# tick-pi-mk-1_0.net
KiCad netlist of a schematic drawn in EAGLE
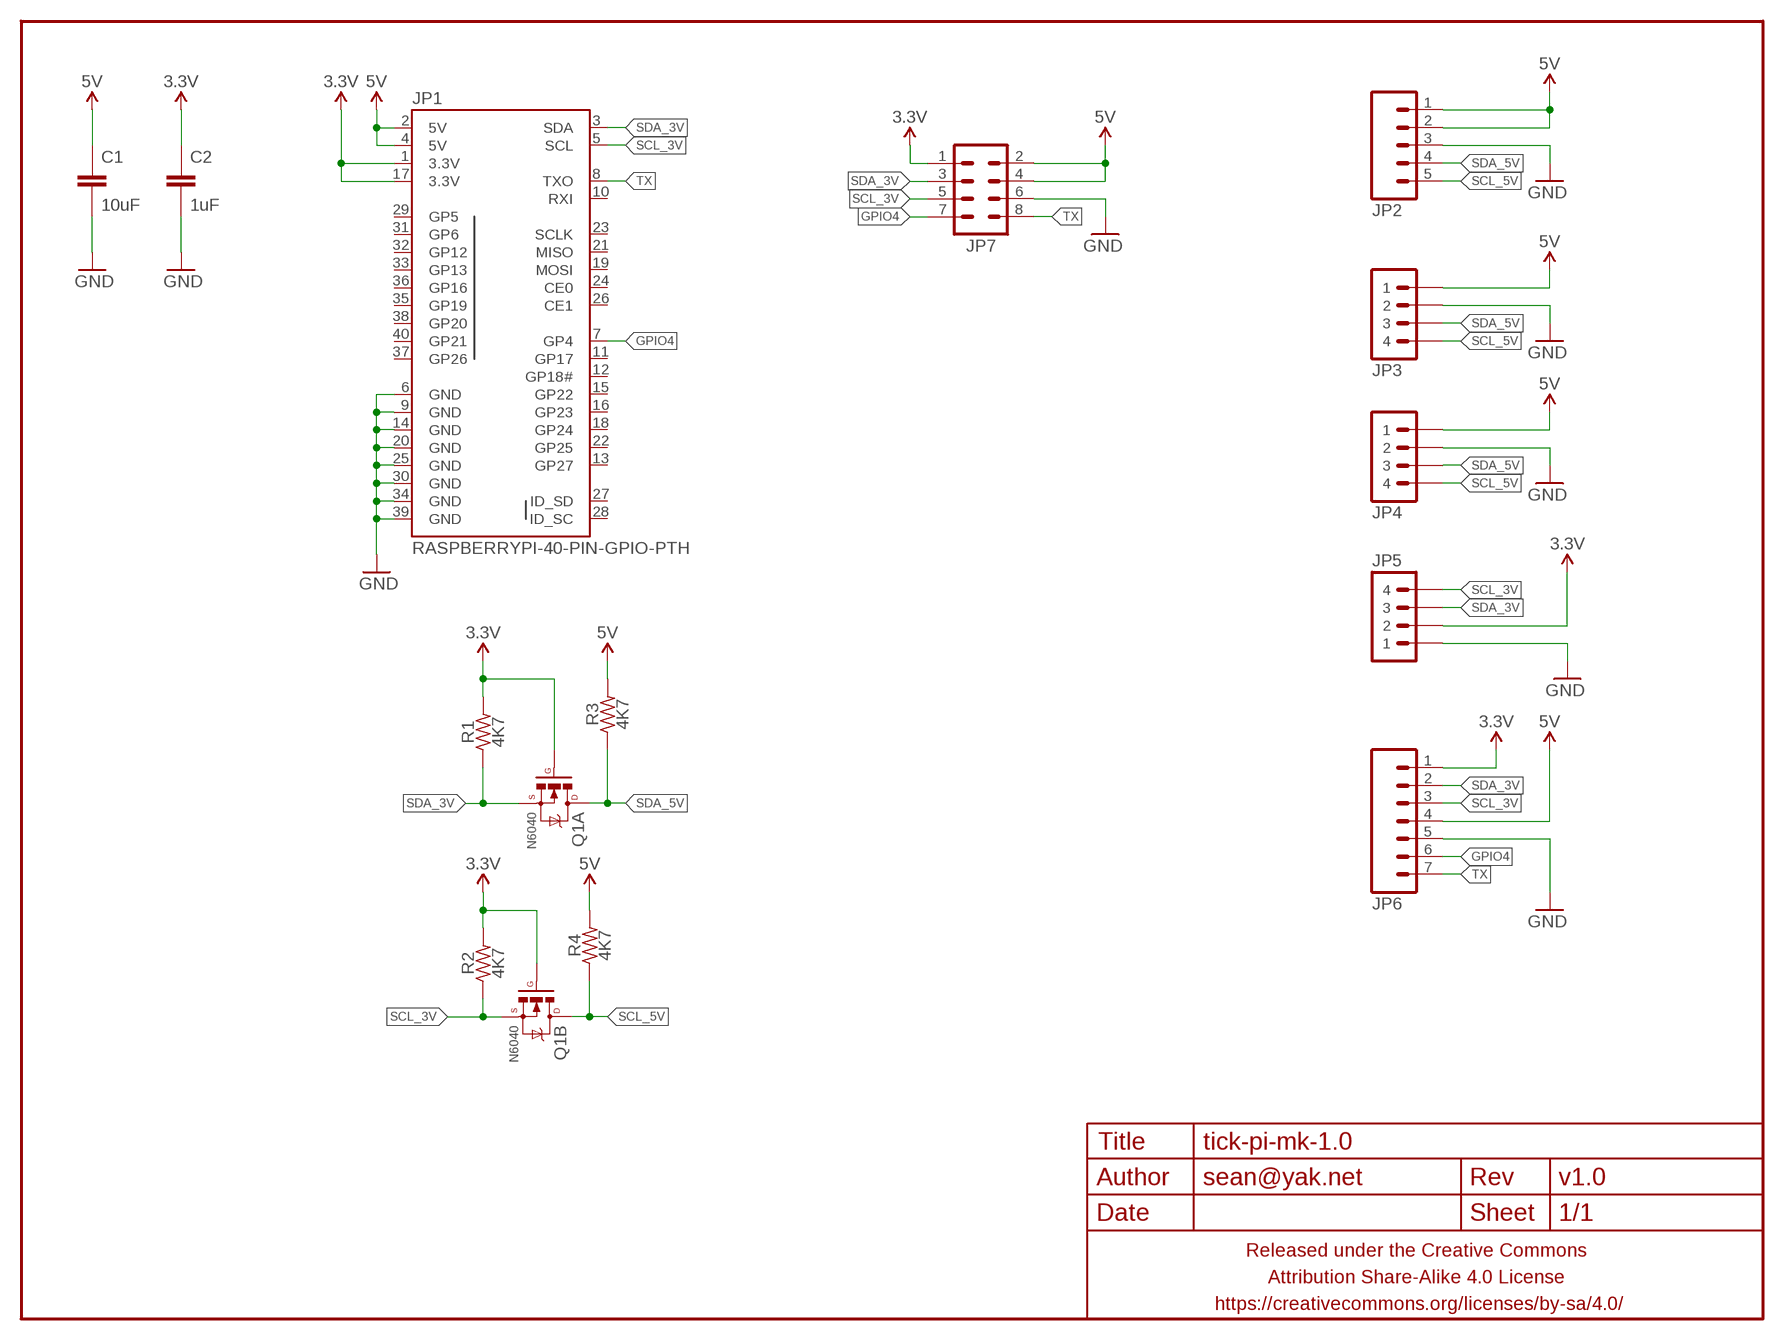
[diagram p0: schematic, sheet 1]

(export (version "E")
  (design (tool "Eeschema 10.0.6"))
  (components
    (comp (ref "C1")
      (value "10uF")
      (footprint "eagle-import:C0805-TIGHTER")
      (libsource (lib "eagle-import") (part "CAPACITOR-CERAMICC0805-TIGHTER"))
    )
    (comp (ref "C2")
      (value "1uF")
      (footprint "eagle-import:C0805-TIGHTER")
      (libsource (lib "eagle-import") (part "CAPACITOR-CERAMICC0805-TIGHTER"))
    )
    (comp (ref "FRAME1")
      (value "FRAME-LETTERNO_PACKAGE")
      (footprint "eagle-import:DUMMY")
      (fields (field (name "DESIGNER") "sean@yak.net") (field (name "VERSION") "v1.0"))
      (libsource (lib "eagle-import") (part "FRAME-LETTERNO_PACKAGE"))
    )
    (comp (ref "JP1")
      (value "RASPBERRYPI-40-PIN-GPIO-PTH")
      (footprint "eagle-import:2X20_PTH")
      (libsource (lib "eagle-import") (part "RASPBERRYPI-40-PIN-GPIO-PTH"))
    )
    (comp (ref "JP2")
      (value "M05PTH-CENTERED-RA-FEMALE")
      (footprint "eagle-import:1X05_PTH_CENTERED_RA_FEMALE")
      (libsource (lib "eagle-import") (part "M05PTH-CENTERED-RA-FEMALE"))
    )
    (comp (ref "JP3")
      (value "M04PTH")
      (footprint "eagle-import:1X04-PTH-VERT")
      (libsource (lib "eagle-import") (part "M04PTH"))
    )
    (comp (ref "JP4")
      (value "M04PTH")
      (footprint "eagle-import:1X04-PTH-VERT")
      (libsource (lib "eagle-import") (part "M04PTH"))
    )
    (comp (ref "JP5")
      (value "M04PTH")
      (footprint "eagle-import:1X04-PTH-VERT")
      (libsource (lib "eagle-import") (part "M04PTH"))
    )
    (comp (ref "JP6")
      (value "M07")
      (footprint "eagle-import:1X07")
      (libsource (lib "eagle-import") (part "M07"))
    )
    (comp (ref "JP7")
      (value "M04X2PTH")
      (footprint "eagle-import:2X4_PTH")
      (libsource (lib "eagle-import") (part "M04X2PTH"))
    )
    (comp (ref "Q1")
      (value "N6040")
      (footprint "eagle-import:SO08")
      (libsource (lib "eagle-import") (part "MOSFET-NCHANNEL-DUALSOIC8"))
    )
    (comp (ref "R1")
      (value "4K7")
      (footprint "eagle-import:R0603")
      (libsource (lib "eagle-import") (part "RESISTORR0603"))
    )
    (comp (ref "R2")
      (value "4K7")
      (footprint "eagle-import:R0603")
      (libsource (lib "eagle-import") (part "RESISTORR0603"))
    )
    (comp (ref "R3")
      (value "4K7")
      (footprint "eagle-import:R0603")
      (libsource (lib "eagle-import") (part "RESISTORR0603"))
    )
    (comp (ref "R4")
      (value "4K7")
      (footprint "eagle-import:R0603")
      (libsource (lib "eagle-import") (part "RESISTORR0603"))
    )
  )
  (nets
    (net (code "1") (name "3.3V") (class "Default")
      (node (ref "C2") (pin "1") (pinfunction "1_1") (pintype "passive"))
      (node (ref "JP1") (pin "1") (pinfunction "3.3V_1") (pintype "power_in"))
      (node (ref "JP1") (pin "17") (pinfunction "3.3V_17") (pintype "power_in"))
      (node (ref "JP5") (pin "2") (pinfunction "2_2") (pintype "passive"))
      (node (ref "JP6") (pin "1") (pinfunction "1_1") (pintype "passive"))
      (node (ref "JP7") (pin "1") (pinfunction "1_1") (pintype "passive"))
      (node (ref "Q1") (pin "2") (pinfunction "G_2") (pintype "passive"))
      (node (ref "Q1") (pin "4") (pinfunction "G_4") (pintype "passive"))
      (node (ref "R1") (pin "2") (pinfunction "2_2") (pintype "passive"))
      (node (ref "R2") (pin "2") (pinfunction "2_2") (pintype "passive"))
    )
    (net (code "2") (name "5V") (class "Default")
      (node (ref "C1") (pin "1") (pinfunction "1_1") (pintype "passive"))
      (node (ref "JP1") (pin "2") (pinfunction "5V_2") (pintype "power_in"))
      (node (ref "JP1") (pin "4") (pinfunction "5V_4") (pintype "power_in"))
      (node (ref "JP2") (pin "1") (pinfunction "1_1") (pintype "passive"))
      (node (ref "JP2") (pin "2") (pinfunction "2_2") (pintype "passive"))
      (node (ref "JP3") (pin "1") (pinfunction "1_1") (pintype "passive"))
      (node (ref "JP4") (pin "1") (pinfunction "1_1") (pintype "passive"))
      (node (ref "JP6") (pin "4") (pinfunction "4_4") (pintype "passive"))
      (node (ref "JP7") (pin "2") (pinfunction "2_2") (pintype "passive"))
      (node (ref "JP7") (pin "4") (pinfunction "4_4") (pintype "passive"))
      (node (ref "R3") (pin "2") (pinfunction "2_2") (pintype "passive"))
      (node (ref "R4") (pin "2") (pinfunction "2_2") (pintype "passive"))
    )
    (net (code "3") (name "GND") (class "Default")
      (node (ref "C1") (pin "2") (pinfunction "2_2") (pintype "passive"))
      (node (ref "C2") (pin "2") (pinfunction "2_2") (pintype "passive"))
      (node (ref "JP1") (pin "14") (pinfunction "GND_14") (pintype "power_in"))
      (node (ref "JP1") (pin "20") (pinfunction "GND_20") (pintype "power_in"))
      (node (ref "JP1") (pin "25") (pinfunction "GND_25") (pintype "power_in"))
      (node (ref "JP1") (pin "30") (pinfunction "GND_30") (pintype "power_in"))
      (node (ref "JP1") (pin "34") (pinfunction "GND_34") (pintype "power_in"))
      (node (ref "JP1") (pin "39") (pinfunction "GND_39") (pintype "power_in"))
      (node (ref "JP1") (pin "6") (pinfunction "GND_6") (pintype "power_in"))
      (node (ref "JP1") (pin "9") (pinfunction "GND_9") (pintype "power_in"))
      (node (ref "JP2") (pin "3") (pinfunction "3_3") (pintype "passive"))
      (node (ref "JP3") (pin "2") (pinfunction "2_2") (pintype "passive"))
      (node (ref "JP4") (pin "2") (pinfunction "2_2") (pintype "passive"))
      (node (ref "JP5") (pin "1") (pinfunction "1_1") (pintype "passive"))
      (node (ref "JP6") (pin "5") (pinfunction "5_5") (pintype "passive"))
      (node (ref "JP7") (pin "6") (pinfunction "6_6") (pintype "passive"))
    )
    (net (code "4") (name "GPIO4") (class "Default")
      (node (ref "JP1") (pin "7") (pinfunction "GP4_7") (pintype "bidirectional"))
      (node (ref "JP6") (pin "6") (pinfunction "6_6") (pintype "passive"))
      (node (ref "JP7") (pin "7") (pinfunction "7_7") (pintype "passive"))
    )
    (net (code "5") (name "SCL_3V") (class "Default")
      (node (ref "JP1") (pin "5") (pinfunction "SCL_5") (pintype "bidirectional"))
      (node (ref "JP5") (pin "4") (pinfunction "4_4") (pintype "passive"))
      (node (ref "JP6") (pin "3") (pinfunction "3_3") (pintype "passive"))
      (node (ref "JP7") (pin "5") (pinfunction "5_5") (pintype "passive"))
      (node (ref "Q1") (pin "3") (pinfunction "S_3") (pintype "passive"))
      (node (ref "R2") (pin "1") (pinfunction "1_1") (pintype "passive"))
    )
    (net (code "6") (name "SCL_5V") (class "Default")
      (node (ref "JP2") (pin "5") (pinfunction "5_5") (pintype "passive"))
      (node (ref "JP3") (pin "4") (pinfunction "4_4") (pintype "passive"))
      (node (ref "JP4") (pin "4") (pinfunction "4_4") (pintype "passive"))
      (node (ref "Q1") (pin "5") (pinfunction "D_5") (pintype "passive"))
      (node (ref "Q1") (pin "6") (pinfunction "D_6") (pintype "passive"))
      (node (ref "R4") (pin "1") (pinfunction "1_1") (pintype "passive"))
    )
    (net (code "7") (name "SDA_3V") (class "Default")
      (node (ref "JP1") (pin "3") (pinfunction "SDA_3") (pintype "bidirectional"))
      (node (ref "JP5") (pin "3") (pinfunction "3_3") (pintype "passive"))
      (node (ref "JP6") (pin "2") (pinfunction "2_2") (pintype "passive"))
      (node (ref "JP7") (pin "3") (pinfunction "3_3") (pintype "passive"))
      (node (ref "Q1") (pin "1") (pinfunction "S_1") (pintype "passive"))
      (node (ref "R1") (pin "1") (pinfunction "1_1") (pintype "passive"))
    )
    (net (code "8") (name "SDA_5V") (class "Default")
      (node (ref "JP2") (pin "4") (pinfunction "4_4") (pintype "passive"))
      (node (ref "JP3") (pin "3") (pinfunction "3_3") (pintype "passive"))
      (node (ref "JP4") (pin "3") (pinfunction "3_3") (pintype "passive"))
      (node (ref "Q1") (pin "7") (pinfunction "D_7") (pintype "passive"))
      (node (ref "Q1") (pin "8") (pinfunction "D_8") (pintype "passive"))
      (node (ref "R3") (pin "1") (pinfunction "1_1") (pintype "passive"))
    )
    (net (code "9") (name "TX") (class "Default")
      (node (ref "JP1") (pin "8") (pinfunction "TXO_8") (pintype "output"))
      (node (ref "JP6") (pin "7") (pinfunction "7_7") (pintype "passive"))
      (node (ref "JP7") (pin "8") (pinfunction "8_8") (pintype "passive"))
    )
    (net (code "10") (name "unconnected-(JP1-CE0-Pad24)") (class "Default")
      (node (ref "JP1") (pin "24") (pinfunction "CE0_24") (pintype "output"))
    )
    (net (code "11") (name "unconnected-(JP1-CE1-Pad26)") (class "Default")
      (node (ref "JP1") (pin "26") (pinfunction "CE1_26") (pintype "output"))
    )
    (net (code "12") (name "unconnected-(JP1-GP5-Pad29)") (class "Default")
      (node (ref "JP1") (pin "29") (pinfunction "GP5_29") (pintype "bidirectional"))
    )
    (net (code "13") (name "unconnected-(JP1-GP6-Pad31)") (class "Default")
      (node (ref "JP1") (pin "31") (pinfunction "GP6_31") (pintype "bidirectional"))
    )
    (net (code "14") (name "unconnected-(JP1-GP12-Pad32)") (class "Default")
      (node (ref "JP1") (pin "32") (pinfunction "GP12_32") (pintype "bidirectional"))
    )
    (net (code "15") (name "unconnected-(JP1-GP13-Pad33)") (class "Default")
      (node (ref "JP1") (pin "33") (pinfunction "GP13_33") (pintype "bidirectional"))
    )
    (net (code "16") (name "unconnected-(JP1-GP16-Pad36)") (class "Default")
      (node (ref "JP1") (pin "36") (pinfunction "GP16_36") (pintype "bidirectional"))
    )
    (net (code "17") (name "unconnected-(JP1-GP17-Pad11)") (class "Default")
      (node (ref "JP1") (pin "11") (pinfunction "GP17_11") (pintype "bidirectional"))
    )
    (net (code "18") (name "unconnected-(JP1-GP18#-Pad12)") (class "Default")
      (node (ref "JP1") (pin "12") (pinfunction "GP18#_12") (pintype "bidirectional"))
    )
    (net (code "19") (name "unconnected-(JP1-GP19-Pad35)") (class "Default")
      (node (ref "JP1") (pin "35") (pinfunction "GP19_35") (pintype "bidirectional"))
    )
    (net (code "20") (name "unconnected-(JP1-GP20-Pad38)") (class "Default")
      (node (ref "JP1") (pin "38") (pinfunction "GP20_38") (pintype "bidirectional"))
    )
    (net (code "21") (name "unconnected-(JP1-GP21-Pad40)") (class "Default")
      (node (ref "JP1") (pin "40") (pinfunction "GP21_40") (pintype "bidirectional"))
    )
    (net (code "22") (name "unconnected-(JP1-GP22-Pad15)") (class "Default")
      (node (ref "JP1") (pin "15") (pinfunction "GP22_15") (pintype "bidirectional"))
    )
    (net (code "23") (name "unconnected-(JP1-GP23-Pad16)") (class "Default")
      (node (ref "JP1") (pin "16") (pinfunction "GP23_16") (pintype "bidirectional"))
    )
    (net (code "24") (name "unconnected-(JP1-GP24-Pad18)") (class "Default")
      (node (ref "JP1") (pin "18") (pinfunction "GP24_18") (pintype "bidirectional"))
    )
    (net (code "25") (name "unconnected-(JP1-GP25-Pad22)") (class "Default")
      (node (ref "JP1") (pin "22") (pinfunction "GP25_22") (pintype "bidirectional"))
    )
    (net (code "26") (name "unconnected-(JP1-GP26-Pad37)") (class "Default")
      (node (ref "JP1") (pin "37") (pinfunction "GP26_37") (pintype "bidirectional"))
    )
    (net (code "27") (name "unconnected-(JP1-GP27-Pad13)") (class "Default")
      (node (ref "JP1") (pin "13") (pinfunction "GP27_13") (pintype "bidirectional"))
    )
    (net (code "28") (name "unconnected-(JP1-ID_SC-Pad28)") (class "Default")
      (node (ref "JP1") (pin "28") (pinfunction "ID_SC_28") (pintype "bidirectional"))
    )
    (net (code "29") (name "unconnected-(JP1-ID_SD-Pad27)") (class "Default")
      (node (ref "JP1") (pin "27") (pinfunction "ID_SD_27") (pintype "bidirectional"))
    )
    (net (code "30") (name "unconnected-(JP1-MISO-Pad21)") (class "Default")
      (node (ref "JP1") (pin "21") (pinfunction "MISO_21") (pintype "input"))
    )
    (net (code "31") (name "unconnected-(JP1-MOSI-Pad19)") (class "Default")
      (node (ref "JP1") (pin "19") (pinfunction "MOSI_19") (pintype "output"))
    )
    (net (code "32") (name "unconnected-(JP1-RXI-Pad10)") (class "Default")
      (node (ref "JP1") (pin "10") (pinfunction "RXI_10") (pintype "input"))
    )
    (net (code "33") (name "unconnected-(JP1-SCLK-Pad23)") (class "Default")
      (node (ref "JP1") (pin "23") (pinfunction "SCLK_23") (pintype "output"))
    )
  )
)
